# 5V_buckboost.net
KiCad netlist of a schematic drawn in EAGLE
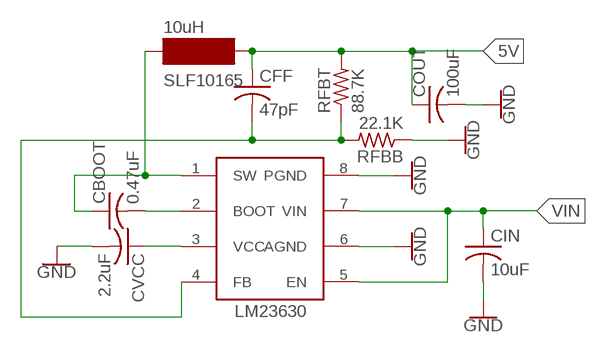
[diagram p0: schematic, sheet 1]

(export (version "E")
  (design (tool "Eeschema 10.0.6"))
  (components
    (comp (ref "CBOOT")
      (value "0.47uF")
      (footprint "eagle-import:C1206")
      (libsource (lib "eagle-import") (part "C-USC1206"))
    )
    (comp (ref "CFF")
      (value "47pF")
      (footprint "eagle-import:C1206")
      (libsource (lib "eagle-import") (part "C-USC1206"))
    )
    (comp (ref "CIN")
      (value "10uF")
      (footprint "eagle-import:C1206")
      (libsource (lib "eagle-import") (part "C-USC1206"))
    )
    (comp (ref "COUT")
      (value "100uF")
      (footprint "eagle-import:C1206")
      (libsource (lib "eagle-import") (part "C-USC1206"))
    )
    (comp (ref "CVCC")
      (value "2.2uF")
      (footprint "eagle-import:C1206")
      (libsource (lib "eagle-import") (part "C-USC1206"))
    )
    (comp (ref "RFBB")
      (value "22.1K")
      (footprint "eagle-import:M1206")
      (libsource (lib "eagle-import") (part "R-US_M1206"))
    )
    (comp (ref "RFBT")
      (value "88.7K")
      (footprint "eagle-import:M1206")
      (libsource (lib "eagle-import") (part "R-US_M1206"))
    )
    (comp (ref "SLF10165")
      (value "10uH")
      (footprint "eagle-import:10.1_10.1")
      (libsource (lib "eagle-import") (part "SLF10165"))
    )
    (comp (ref "U$1")
      (value "LM23630")
      (footprint "eagle-import:SOIC127P602X168-8N")
      (libsource (lib "eagle-import") (part "LM23630"))
    )
  )
  (nets
    (net (code "1") (name "5V") (class "Default")
      (node (ref "CFF") (pin "1") (pinfunction "1_1") (pintype "passive"))
      (node (ref "COUT") (pin "1") (pinfunction "1_1") (pintype "passive"))
      (node (ref "RFBT") (pin "2") (pinfunction "2_2") (pintype "passive"))
      (node (ref "SLF10165") (pin "P$2") (pinfunction "P$2_P$2") (pintype "bidirectional"))
    )
    (net (code "2") (name "GND") (class "Default")
      (node (ref "CIN") (pin "2") (pinfunction "2_2") (pintype "passive"))
      (node (ref "COUT") (pin "2") (pinfunction "2_2") (pintype "passive"))
      (node (ref "CVCC") (pin "2") (pinfunction "2_2") (pintype "passive"))
      (node (ref "RFBB") (pin "1") (pinfunction "1_1") (pintype "passive"))
      (node (ref "U$1") (pin "6") (pinfunction "AGND_6") (pintype "bidirectional"))
      (node (ref "U$1") (pin "8") (pinfunction "PGND_8") (pintype "bidirectional"))
    )
    (net (code "3") (name "Net-(U$1-BOOT)") (class "Default")
      (node (ref "CBOOT") (pin "2") (pinfunction "2_2") (pintype "passive"))
      (node (ref "U$1") (pin "2") (pinfunction "BOOT_2") (pintype "bidirectional"))
    )
    (net (code "4") (name "Net-(U$1-FB)") (class "Default")
      (node (ref "CFF") (pin "2") (pinfunction "2_2") (pintype "passive"))
      (node (ref "RFBB") (pin "2") (pinfunction "2_2") (pintype "passive"))
      (node (ref "RFBT") (pin "1") (pinfunction "1_1") (pintype "passive"))
      (node (ref "U$1") (pin "4") (pinfunction "FB_4") (pintype "bidirectional"))
    )
    (net (code "5") (name "Net-(U$1-SW)") (class "Default")
      (node (ref "CBOOT") (pin "1") (pinfunction "1_1") (pintype "passive"))
      (node (ref "SLF10165") (pin "P$1") (pinfunction "P$1_P$1") (pintype "bidirectional"))
      (node (ref "U$1") (pin "1") (pinfunction "SW_1") (pintype "bidirectional"))
    )
    (net (code "6") (name "Net-(U$1-VCC)") (class "Default")
      (node (ref "CVCC") (pin "1") (pinfunction "1_1") (pintype "passive"))
      (node (ref "U$1") (pin "3") (pinfunction "VCC_3") (pintype "bidirectional"))
    )
    (net (code "7") (name "VIN") (class "Default")
      (node (ref "CIN") (pin "1") (pinfunction "1_1") (pintype "passive"))
      (node (ref "U$1") (pin "5") (pinfunction "EN_5") (pintype "bidirectional"))
      (node (ref "U$1") (pin "7") (pinfunction "VIN_7") (pintype "bidirectional"))
    )
  )
)
